# schematic.net
KiCad netlist of a schematic drawn in Altium Designer
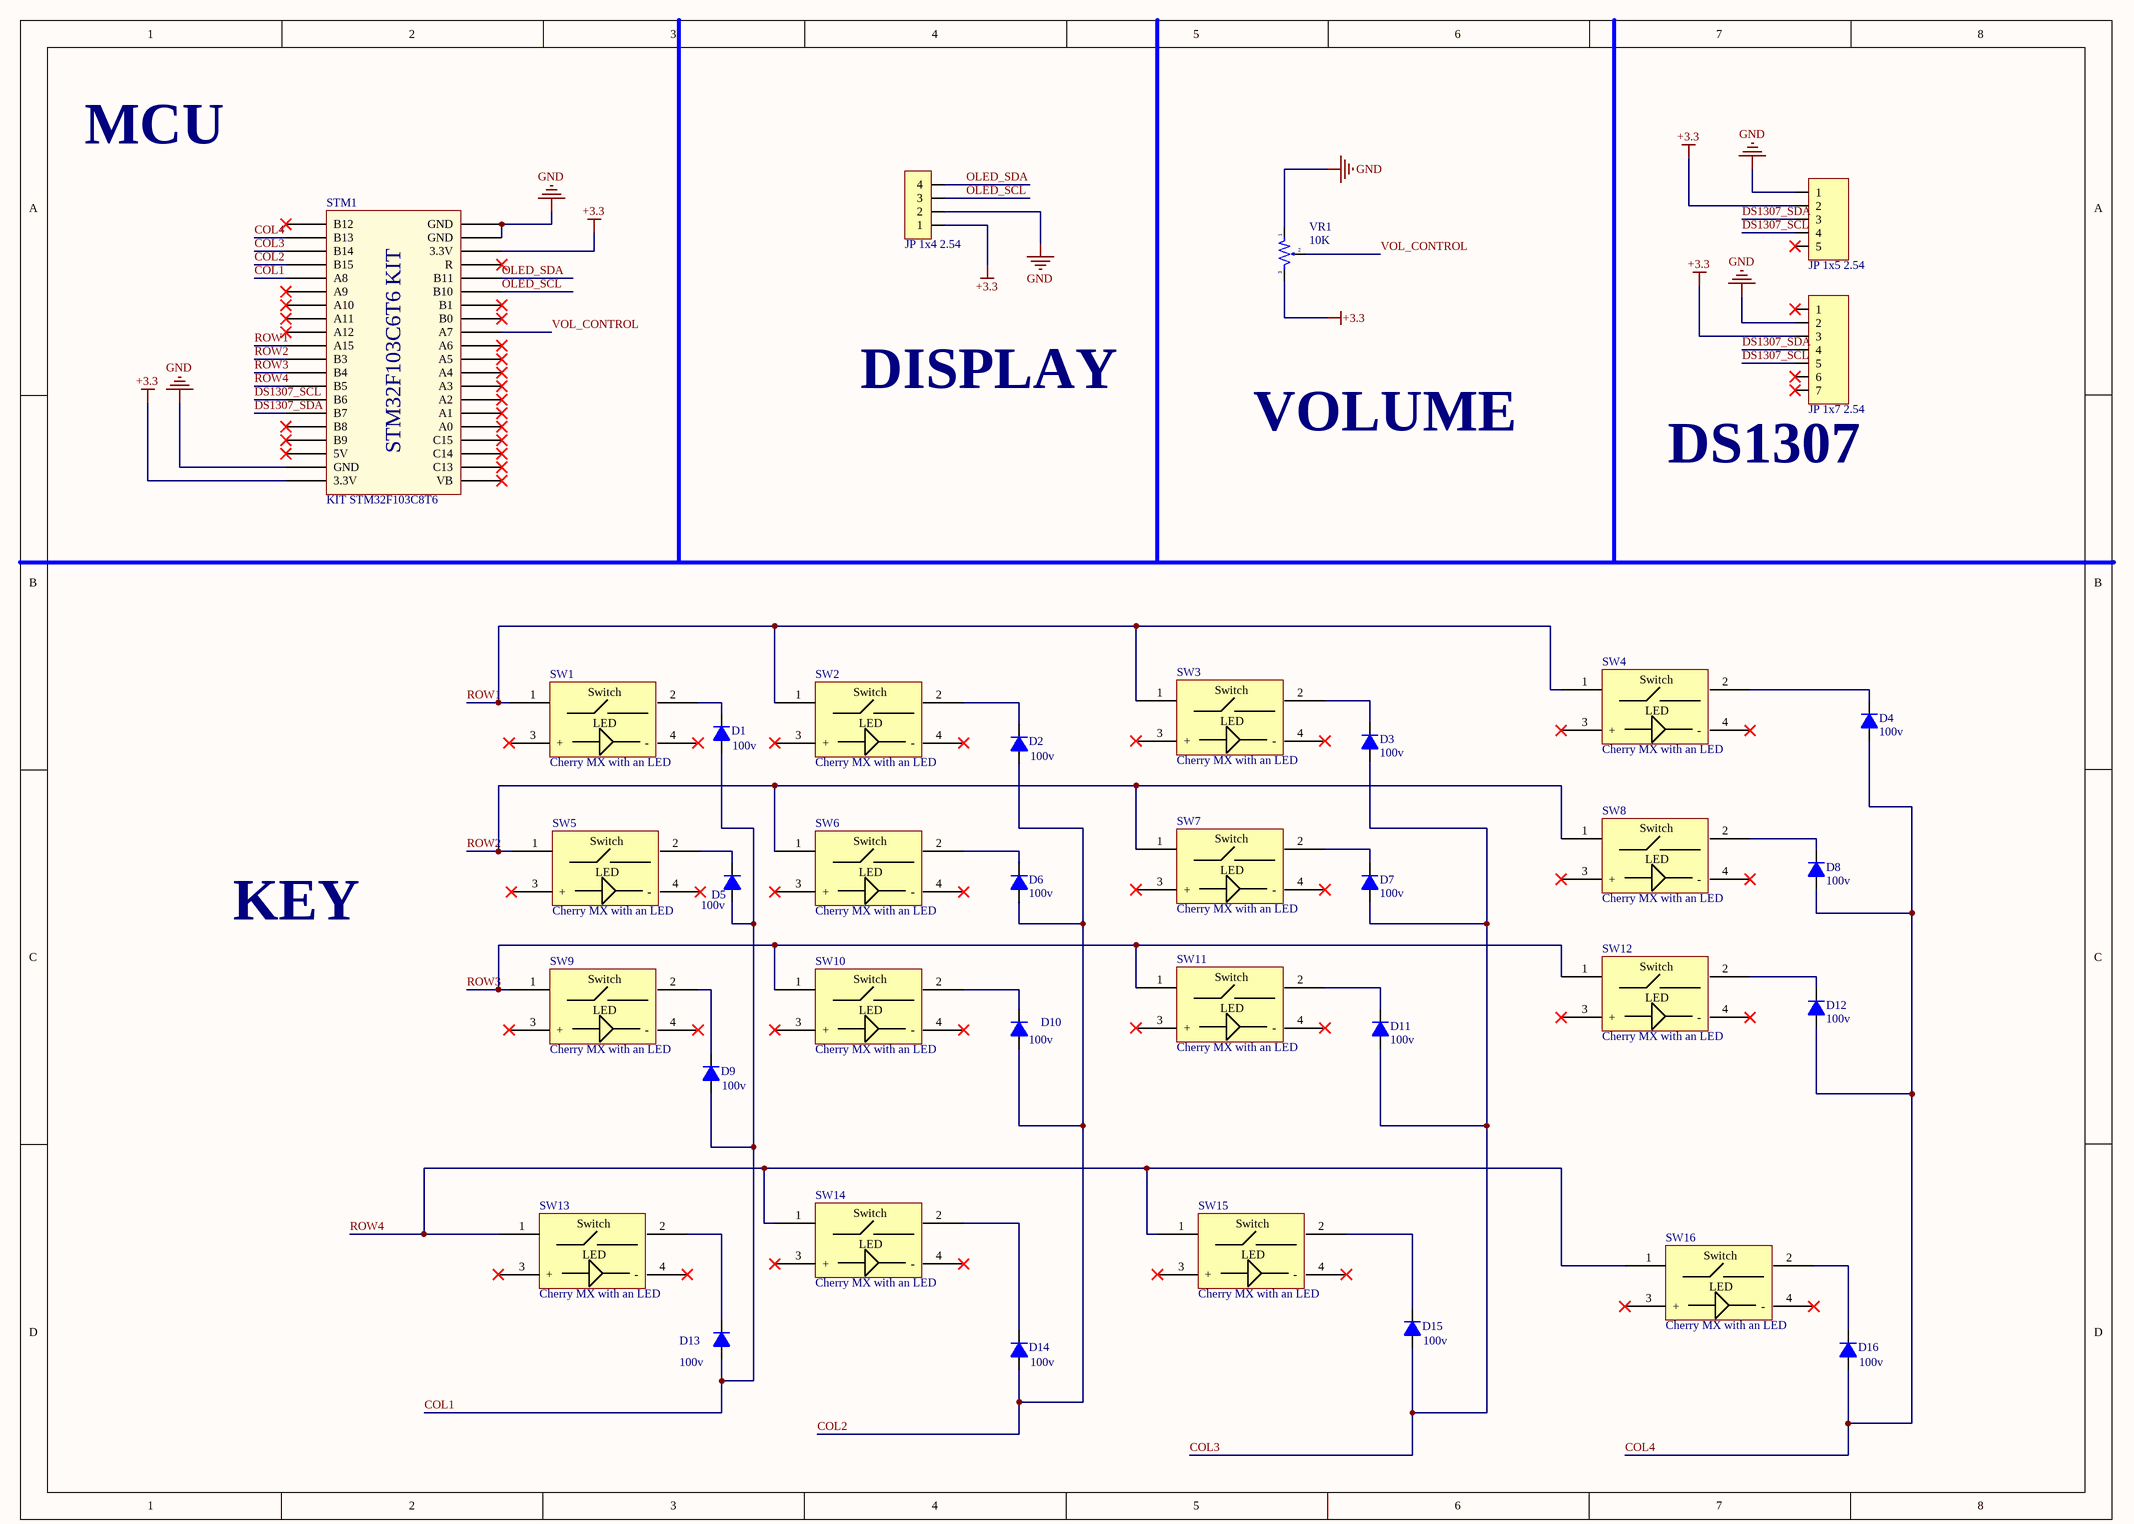
[diagram p0: schematic.SchDoc]

(export (version "E")
  (design (tool "Eeschema 10.0.6"))
  (components
    (comp (ref "D1")
      (value "100v")
      (footprint "DIODE 0.5A")
      (description "Cắm")
      (libsource (lib "Altium_Lib_by_KhueNguyenCreator") (part "Diode 1N4148"))
    )
    (comp (ref "D2")
      (value "100v")
      (footprint "DIODE 0.5A")
      (description "Cắm")
      (libsource (lib "Altium_Lib_by_KhueNguyenCreator") (part "Diode 1N4148"))
    )
    (comp (ref "D3")
      (value "100v")
      (footprint "DIODE 0.5A")
      (description "Cắm")
      (libsource (lib "Altium_Lib_by_KhueNguyenCreator") (part "Diode 1N4148"))
    )
    (comp (ref "D4")
      (value "100v")
      (footprint "DIODE 0.5A")
      (description "Cắm")
      (libsource (lib "Altium_Lib_by_KhueNguyenCreator") (part "Diode 1N4148"))
    )
    (comp (ref "D5")
      (value "100v")
      (footprint "DIODE 0.5A")
      (description "Cắm")
      (libsource (lib "Altium_Lib_by_KhueNguyenCreator") (part "Diode 1N4148"))
    )
    (comp (ref "D6")
      (value "100v")
      (footprint "DIODE 0.5A")
      (description "Cắm")
      (libsource (lib "Altium_Lib_by_KhueNguyenCreator") (part "Diode 1N4148"))
    )
    (comp (ref "D7")
      (value "100v")
      (footprint "DIODE 0.5A")
      (description "Cắm")
      (libsource (lib "Altium_Lib_by_KhueNguyenCreator") (part "Diode 1N4148"))
    )
    (comp (ref "D8")
      (value "100v")
      (footprint "DIODE 0.5A")
      (description "Cắm")
      (libsource (lib "Altium_Lib_by_KhueNguyenCreator") (part "Diode 1N4148"))
    )
    (comp (ref "D9")
      (value "100v")
      (footprint "DIODE 0.5A")
      (description "Cắm")
      (libsource (lib "Altium_Lib_by_KhueNguyenCreator") (part "Diode 1N4148"))
    )
    (comp (ref "D10")
      (value "100v")
      (footprint "DIODE 0.5A")
      (description "Cắm")
      (libsource (lib "Altium_Lib_by_KhueNguyenCreator") (part "Diode 1N4148"))
    )
    (comp (ref "D11")
      (value "100v")
      (footprint "DIODE 0.5A")
      (description "Cắm")
      (libsource (lib "Altium_Lib_by_KhueNguyenCreator") (part "Diode 1N4148"))
    )
    (comp (ref "D12")
      (value "100v")
      (footprint "DIODE 0.5A")
      (description "Cắm")
      (libsource (lib "Altium_Lib_by_KhueNguyenCreator") (part "Diode 1N4148"))
    )
    (comp (ref "D13")
      (value "100v")
      (footprint "DIODE 0.5A")
      (description "Cắm")
      (libsource (lib "Altium_Lib_by_KhueNguyenCreator") (part "Diode 1N4148"))
    )
    (comp (ref "D14")
      (value "100v")
      (footprint "DIODE 0.5A")
      (description "Cắm")
      (libsource (lib "Altium_Lib_by_KhueNguyenCreator") (part "Diode 1N4148"))
    )
    (comp (ref "D15")
      (value "100v")
      (footprint "DIODE 0.5A")
      (description "Cắm")
      (libsource (lib "Altium_Lib_by_KhueNguyenCreator") (part "Diode 1N4148"))
    )
    (comp (ref "D16")
      (value "100v")
      (footprint "DIODE 0.5A")
      (description "Cắm")
      (libsource (lib "Altium_Lib_by_KhueNguyenCreator") (part "Diode 1N4148"))
    )
    (comp (ref "JP1")
      (value "JP 1x4 2.54")
      (footprint "JP 1x4 CT")
      (description "Cắm")
      (libsource (lib "Altium_Lib_by_KhueNguyenCreator") (part "JP 1x4 2.54 Cai Thang"))
    )
    (comp (ref "JP2")
      (value "JP 1x5 2.54")
      (footprint "JP 1x5 CT")
      (description "Cắm")
      (libsource (lib "Altium_Lib_by_KhueNguyenCreator") (part "JP 1x5 2.54 Cai Thang"))
    )
    (comp (ref "JP3")
      (value "JP 1x7 2.54")
      (footprint "JP 1x7 CT")
      (description "Cắm")
      (libsource (lib "Altium_Lib_by_KhueNguyenCreator") (part "JP 1x7 2.54 Cai Thang"))
    )
    (comp (ref "STM1")
      (value "KIT STM32F103C8T6")
      (footprint "STM32F103 KIT")
      (description "KIT STM32F103C8T6 Bluepill")
      (libsource (lib "Altium_Lib_by_KhueNguyenCreator") (part "STM32f103 Bluepill"))
    )
    (comp (ref "SW1")
      (value "Cherry MX with an LED")
      (footprint "MX_Cherry_LED")
      (libsource (lib "PlumPot_Library") (part "MX_Cherry_LED"))
    )
    (comp (ref "SW2")
      (value "Cherry MX with an LED")
      (footprint "MX_Cherry_LED")
      (libsource (lib "PlumPot_Library") (part "MX_Cherry_LED"))
    )
    (comp (ref "SW3")
      (value "Cherry MX with an LED")
      (footprint "MX_Cherry_LED")
      (libsource (lib "PlumPot_Library") (part "MX_Cherry_LED"))
    )
    (comp (ref "SW4")
      (value "Cherry MX with an LED")
      (footprint "MX_Cherry_LED")
      (libsource (lib "PlumPot_Library") (part "MX_Cherry_LED"))
    )
    (comp (ref "SW5")
      (value "Cherry MX with an LED")
      (footprint "MX_Cherry_LED")
      (libsource (lib "PlumPot_Library") (part "MX_Cherry_LED"))
    )
    (comp (ref "SW6")
      (value "Cherry MX with an LED")
      (footprint "MX_Cherry_LED")
      (libsource (lib "PlumPot_Library") (part "MX_Cherry_LED"))
    )
    (comp (ref "SW7")
      (value "Cherry MX with an LED")
      (footprint "MX_Cherry_LED")
      (libsource (lib "PlumPot_Library") (part "MX_Cherry_LED"))
    )
    (comp (ref "SW8")
      (value "Cherry MX with an LED")
      (footprint "MX_Cherry_LED")
      (libsource (lib "PlumPot_Library") (part "MX_Cherry_LED"))
    )
    (comp (ref "SW9")
      (value "Cherry MX with an LED")
      (footprint "MX_Cherry_LED")
      (libsource (lib "PlumPot_Library") (part "MX_Cherry_LED"))
    )
    (comp (ref "SW10")
      (value "Cherry MX with an LED")
      (footprint "MX_Cherry_LED")
      (libsource (lib "PlumPot_Library") (part "MX_Cherry_LED"))
    )
    (comp (ref "SW11")
      (value "Cherry MX with an LED")
      (footprint "MX_Cherry_LED")
      (libsource (lib "PlumPot_Library") (part "MX_Cherry_LED"))
    )
    (comp (ref "SW12")
      (value "Cherry MX with an LED")
      (footprint "MX_Cherry_LED")
      (libsource (lib "PlumPot_Library") (part "MX_Cherry_LED"))
    )
    (comp (ref "SW13")
      (value "Cherry MX with an LED")
      (footprint "MX_Cherry_LED")
      (libsource (lib "PlumPot_Library") (part "MX_Cherry_LED"))
    )
    (comp (ref "SW14")
      (value "Cherry MX with an LED")
      (footprint "MX_Cherry_LED")
      (libsource (lib "PlumPot_Library") (part "MX_Cherry_LED"))
    )
    (comp (ref "SW15")
      (value "Cherry MX with an LED")
      (footprint "MX_Cherry_LED")
      (libsource (lib "PlumPot_Library") (part "MX_Cherry_LED"))
    )
    (comp (ref "SW16")
      (value "Cherry MX with an LED")
      (footprint "MX_Cherry_LED")
      (libsource (lib "PlumPot_Library") (part "MX_Cherry_LED"))
    )
    (comp (ref "VR1")
      (value "10K")
      (footprint "Bien Tro Volume Don")
      (description "Cắm")
      (libsource (lib "Altium_Lib_by_KhueNguyenCreator") (part "Triet Ap Don 10k"))
    )
  )
  (nets
    (net (code "1") (name "+3.3") (class "Default")
      (node (ref "JP1") (pin "1") (pinfunction "1_1") (pintype "passive"))
      (node (ref "JP2") (pin "2") (pinfunction "2_2") (pintype "passive"))
      (node (ref "JP3") (pin "3") (pinfunction "3_3") (pintype "passive"))
      (node (ref "STM1") (pin "20") (pinfunction "3.3V_20") (pintype "passive"))
      (node (ref "STM1") (pin "38") (pinfunction "3.3V_38") (pintype "passive"))
      (node (ref "VR1") (pin "3") (pinfunction "3_3") (pintype "passive"))
    )
    (net (code "2") (name "/COL1") (class "Default")
      (node (ref "D1") (pin "1") (pinfunction "A_1") (pintype "passive"))
      (node (ref "D13") (pin "1") (pinfunction "A_1") (pintype "passive"))
      (node (ref "D5") (pin "1") (pinfunction "A_1") (pintype "passive"))
      (node (ref "D9") (pin "1") (pinfunction "A_1") (pintype "passive"))
      (node (ref "STM1") (pin "5") (pinfunction "A8_5") (pintype "passive"))
    )
    (net (code "3") (name "/COL2") (class "Default")
      (node (ref "D10") (pin "1") (pinfunction "A_1") (pintype "passive"))
      (node (ref "D14") (pin "1") (pinfunction "A_1") (pintype "passive"))
      (node (ref "D2") (pin "1") (pinfunction "A_1") (pintype "passive"))
      (node (ref "D6") (pin "1") (pinfunction "A_1") (pintype "passive"))
      (node (ref "STM1") (pin "4") (pinfunction "B15_4") (pintype "passive"))
    )
    (net (code "4") (name "/COL3") (class "Default")
      (node (ref "D11") (pin "1") (pinfunction "A_1") (pintype "passive"))
      (node (ref "D15") (pin "1") (pinfunction "A_1") (pintype "passive"))
      (node (ref "D3") (pin "1") (pinfunction "A_1") (pintype "passive"))
      (node (ref "D7") (pin "1") (pinfunction "A_1") (pintype "passive"))
      (node (ref "STM1") (pin "3") (pinfunction "B14_3") (pintype "passive"))
    )
    (net (code "5") (name "/COL4") (class "Default")
      (node (ref "D12") (pin "1") (pinfunction "A_1") (pintype "passive"))
      (node (ref "D16") (pin "1") (pinfunction "A_1") (pintype "passive"))
      (node (ref "D4") (pin "1") (pinfunction "A_1") (pintype "passive"))
      (node (ref "D8") (pin "1") (pinfunction "A_1") (pintype "passive"))
      (node (ref "STM1") (pin "2") (pinfunction "B13_2") (pintype "passive"))
    )
    (net (code "6") (name "/DS1307_SCL") (class "Default")
      (node (ref "JP2") (pin "4") (pinfunction "4_4") (pintype "passive"))
      (node (ref "JP3") (pin "5") (pinfunction "5_5") (pintype "passive"))
      (node (ref "STM1") (pin "14") (pinfunction "B6_14") (pintype "passive"))
    )
    (net (code "7") (name "/DS1307_SDA") (class "Default")
      (node (ref "JP2") (pin "3") (pinfunction "3_3") (pintype "passive"))
      (node (ref "JP3") (pin "4") (pinfunction "4_4") (pintype "passive"))
      (node (ref "STM1") (pin "15") (pinfunction "B7_15") (pintype "passive"))
    )
    (net (code "8") (name "/OLED_SCL") (class "Default")
      (node (ref "JP1") (pin "3") (pinfunction "3_3") (pintype "passive"))
      (node (ref "STM1") (pin "35") (pinfunction "B10_35") (pintype "passive"))
    )
    (net (code "9") (name "/OLED_SDA") (class "Default")
      (node (ref "JP1") (pin "4") (pinfunction "4_4") (pintype "passive"))
      (node (ref "STM1") (pin "36") (pinfunction "B11_36") (pintype "passive"))
    )
    (net (code "10") (name "/ROW1") (class "Default")
      (node (ref "STM1") (pin "10") (pinfunction "A15_10") (pintype "passive"))
      (node (ref "SW1") (pin "1") (pintype "passive"))
      (node (ref "SW2") (pin "1") (pintype "passive"))
      (node (ref "SW3") (pin "1") (pintype "passive"))
      (node (ref "SW4") (pin "1") (pintype "passive"))
    )
    (net (code "11") (name "/ROW2") (class "Default")
      (node (ref "STM1") (pin "11") (pinfunction "B3_11") (pintype "passive"))
      (node (ref "SW5") (pin "1") (pintype "passive"))
      (node (ref "SW6") (pin "1") (pintype "passive"))
      (node (ref "SW7") (pin "1") (pintype "passive"))
      (node (ref "SW8") (pin "1") (pintype "passive"))
    )
    (net (code "12") (name "/ROW3") (class "Default")
      (node (ref "STM1") (pin "12") (pinfunction "B4_12") (pintype "passive"))
      (node (ref "SW10") (pin "1") (pintype "passive"))
      (node (ref "SW11") (pin "1") (pintype "passive"))
      (node (ref "SW12") (pin "1") (pintype "passive"))
      (node (ref "SW9") (pin "1") (pintype "passive"))
    )
    (net (code "13") (name "/ROW4") (class "Default")
      (node (ref "STM1") (pin "13") (pinfunction "B5_13") (pintype "passive"))
      (node (ref "SW13") (pin "1") (pintype "passive"))
      (node (ref "SW14") (pin "1") (pintype "passive"))
      (node (ref "SW15") (pin "1") (pintype "passive"))
      (node (ref "SW16") (pin "1") (pintype "passive"))
    )
    (net (code "14") (name "/VOL_CONTROL") (class "Default")
      (node (ref "STM1") (pin "32") (pinfunction "A7_32") (pintype "passive"))
      (node (ref "VR1") (pin "2") (pinfunction "2_2") (pintype "passive"))
    )
    (net (code "15") (name "GND") (class "Default")
      (node (ref "JP1") (pin "2") (pinfunction "2_2") (pintype "passive"))
      (node (ref "JP2") (pin "1") (pinfunction "1_1") (pintype "passive"))
      (node (ref "JP3") (pin "2") (pinfunction "2_2") (pintype "passive"))
      (node (ref "STM1") (pin "19") (pinfunction "GND_19") (pintype "passive"))
      (node (ref "STM1") (pin "39") (pinfunction "GND_39") (pintype "passive"))
      (node (ref "STM1") (pin "40") (pinfunction "GND_40") (pintype "passive"))
      (node (ref "VR1") (pin "1") (pinfunction "1_1") (pintype "passive"))
    )
    (net (code "16") (name "Net-(D1-K)") (class "Default")
      (node (ref "D1") (pin "2") (pinfunction "K_2") (pintype "passive"))
      (node (ref "SW1") (pin "2") (pintype "passive"))
    )
    (net (code "17") (name "Net-(D2-K)") (class "Default")
      (node (ref "D2") (pin "2") (pinfunction "K_2") (pintype "passive"))
      (node (ref "SW2") (pin "2") (pintype "passive"))
    )
    (net (code "18") (name "Net-(D3-K)") (class "Default")
      (node (ref "D3") (pin "2") (pinfunction "K_2") (pintype "passive"))
      (node (ref "SW3") (pin "2") (pintype "passive"))
    )
    (net (code "19") (name "Net-(D4-K)") (class "Default")
      (node (ref "D4") (pin "2") (pinfunction "K_2") (pintype "passive"))
      (node (ref "SW4") (pin "2") (pintype "passive"))
    )
    (net (code "20") (name "Net-(D5-K)") (class "Default")
      (node (ref "D5") (pin "2") (pinfunction "K_2") (pintype "passive"))
      (node (ref "SW5") (pin "2") (pintype "passive"))
    )
    (net (code "21") (name "Net-(D6-K)") (class "Default")
      (node (ref "D6") (pin "2") (pinfunction "K_2") (pintype "passive"))
      (node (ref "SW6") (pin "2") (pintype "passive"))
    )
    (net (code "22") (name "Net-(D7-K)") (class "Default")
      (node (ref "D7") (pin "2") (pinfunction "K_2") (pintype "passive"))
      (node (ref "SW7") (pin "2") (pintype "passive"))
    )
    (net (code "23") (name "Net-(D8-K)") (class "Default")
      (node (ref "D8") (pin "2") (pinfunction "K_2") (pintype "passive"))
      (node (ref "SW8") (pin "2") (pintype "passive"))
    )
    (net (code "24") (name "Net-(D9-K)") (class "Default")
      (node (ref "D9") (pin "2") (pinfunction "K_2") (pintype "passive"))
      (node (ref "SW9") (pin "2") (pintype "passive"))
    )
    (net (code "25") (name "Net-(D10-K)") (class "Default")
      (node (ref "D10") (pin "2") (pinfunction "K_2") (pintype "passive"))
      (node (ref "SW10") (pin "2") (pintype "passive"))
    )
    (net (code "26") (name "Net-(D11-K)") (class "Default")
      (node (ref "D11") (pin "2") (pinfunction "K_2") (pintype "passive"))
      (node (ref "SW11") (pin "2") (pintype "passive"))
    )
    (net (code "27") (name "Net-(D12-K)") (class "Default")
      (node (ref "D12") (pin "2") (pinfunction "K_2") (pintype "passive"))
      (node (ref "SW12") (pin "2") (pintype "passive"))
    )
    (net (code "28") (name "Net-(D13-K)") (class "Default")
      (node (ref "D13") (pin "2") (pinfunction "K_2") (pintype "passive"))
      (node (ref "SW13") (pin "2") (pintype "passive"))
    )
    (net (code "29") (name "Net-(D14-K)") (class "Default")
      (node (ref "D14") (pin "2") (pinfunction "K_2") (pintype "passive"))
      (node (ref "SW14") (pin "2") (pintype "passive"))
    )
    (net (code "30") (name "Net-(D15-K)") (class "Default")
      (node (ref "D15") (pin "2") (pinfunction "K_2") (pintype "passive"))
      (node (ref "SW15") (pin "2") (pintype "passive"))
    )
    (net (code "31") (name "Net-(D16-K)") (class "Default")
      (node (ref "D16") (pin "2") (pinfunction "K_2") (pintype "passive"))
      (node (ref "SW16") (pin "2") (pintype "passive"))
    )
    (net (code "32") (name "unconnected-(JP2-Pad5)") (class "Default")
      (node (ref "JP2") (pin "5") (pinfunction "5_5") (pintype "passive+no_connect"))
    )
    (net (code "33") (name "unconnected-(JP3-Pad1)") (class "Default")
      (node (ref "JP3") (pin "1") (pinfunction "1_1") (pintype "passive+no_connect"))
    )
    (net (code "34") (name "unconnected-(JP3-Pad6)") (class "Default")
      (node (ref "JP3") (pin "6") (pinfunction "6_6") (pintype "passive+no_connect"))
    )
    (net (code "35") (name "unconnected-(JP3-Pad7)") (class "Default")
      (node (ref "JP3") (pin "7") (pinfunction "7_7") (pintype "passive+no_connect"))
    )
    (net (code "36") (name "unconnected-(STM1-5V-Pad18)") (class "Default")
      (node (ref "STM1") (pin "18") (pinfunction "5V_18") (pintype "passive+no_connect"))
    )
    (net (code "37") (name "unconnected-(STM1-A0-Pad25)") (class "Default")
      (node (ref "STM1") (pin "25") (pinfunction "A0_25") (pintype "passive+no_connect"))
    )
    (net (code "38") (name "unconnected-(STM1-A1-Pad26)") (class "Default")
      (node (ref "STM1") (pin "26") (pinfunction "A1_26") (pintype "passive+no_connect"))
    )
    (net (code "39") (name "unconnected-(STM1-A2-Pad27)") (class "Default")
      (node (ref "STM1") (pin "27") (pinfunction "A2_27") (pintype "passive+no_connect"))
    )
    (net (code "40") (name "unconnected-(STM1-A3-Pad28)") (class "Default")
      (node (ref "STM1") (pin "28") (pinfunction "A3_28") (pintype "passive+no_connect"))
    )
    (net (code "41") (name "unconnected-(STM1-A4-Pad29)") (class "Default")
      (node (ref "STM1") (pin "29") (pinfunction "A4_29") (pintype "passive+no_connect"))
    )
    (net (code "42") (name "unconnected-(STM1-A5-Pad30)") (class "Default")
      (node (ref "STM1") (pin "30") (pinfunction "A5_30") (pintype "passive+no_connect"))
    )
    (net (code "43") (name "unconnected-(STM1-A6-Pad31)") (class "Default")
      (node (ref "STM1") (pin "31") (pinfunction "A6_31") (pintype "passive+no_connect"))
    )
    (net (code "44") (name "unconnected-(STM1-A9-Pad6)") (class "Default")
      (node (ref "STM1") (pin "6") (pinfunction "A9_6") (pintype "passive+no_connect"))
    )
    (net (code "45") (name "unconnected-(STM1-A10-Pad7)") (class "Default")
      (node (ref "STM1") (pin "7") (pinfunction "A10_7") (pintype "passive+no_connect"))
    )
    (net (code "46") (name "unconnected-(STM1-A11-Pad8)") (class "Default")
      (node (ref "STM1") (pin "8") (pinfunction "A11_8") (pintype "passive+no_connect"))
    )
    (net (code "47") (name "unconnected-(STM1-A12-Pad9)") (class "Default")
      (node (ref "STM1") (pin "9") (pinfunction "A12_9") (pintype "passive+no_connect"))
    )
    (net (code "48") (name "unconnected-(STM1-B0-Pad33)") (class "Default")
      (node (ref "STM1") (pin "33") (pinfunction "B0_33") (pintype "passive+no_connect"))
    )
    (net (code "49") (name "unconnected-(STM1-B1-Pad34)") (class "Default")
      (node (ref "STM1") (pin "34") (pinfunction "B1_34") (pintype "passive+no_connect"))
    )
    (net (code "50") (name "unconnected-(STM1-B8-Pad16)") (class "Default")
      (node (ref "STM1") (pin "16") (pinfunction "B8_16") (pintype "passive+no_connect"))
    )
    (net (code "51") (name "unconnected-(STM1-B9-Pad17)") (class "Default")
      (node (ref "STM1") (pin "17") (pinfunction "B9_17") (pintype "passive+no_connect"))
    )
    (net (code "52") (name "unconnected-(STM1-B12-Pad1)") (class "Default")
      (node (ref "STM1") (pin "1") (pinfunction "B12_1") (pintype "passive+no_connect"))
    )
    (net (code "53") (name "unconnected-(STM1-C13-Pad22)") (class "Default")
      (node (ref "STM1") (pin "22") (pinfunction "C13_22") (pintype "passive+no_connect"))
    )
    (net (code "54") (name "unconnected-(STM1-C14-Pad23)") (class "Default")
      (node (ref "STM1") (pin "23") (pinfunction "C14_23") (pintype "passive+no_connect"))
    )
    (net (code "55") (name "unconnected-(STM1-C15-Pad24)") (class "Default")
      (node (ref "STM1") (pin "24") (pinfunction "C15_24") (pintype "passive+no_connect"))
    )
    (net (code "56") (name "unconnected-(STM1-R-Pad37)") (class "Default")
      (node (ref "STM1") (pin "37") (pinfunction "R_37") (pintype "passive+no_connect"))
    )
    (net (code "57") (name "unconnected-(STM1-VB-Pad21)") (class "Default")
      (node (ref "STM1") (pin "21") (pinfunction "VB_21") (pintype "passive+no_connect"))
    )
    (net (code "58") (name "unconnected-(SW1-+-Pad3)") (class "Default")
      (node (ref "SW1") (pin "3") (pinfunction "+_3") (pintype "passive+no_connect"))
    )
    (net (code "59") (name "unconnected-(SW1---Pad4)") (class "Default")
      (node (ref "SW1") (pin "4") (pinfunction "-_4") (pintype "passive+no_connect"))
    )
    (net (code "60") (name "unconnected-(SW2-+-Pad3)") (class "Default")
      (node (ref "SW2") (pin "3") (pinfunction "+_3") (pintype "passive+no_connect"))
    )
    (net (code "61") (name "unconnected-(SW2---Pad4)") (class "Default")
      (node (ref "SW2") (pin "4") (pinfunction "-_4") (pintype "passive+no_connect"))
    )
    (net (code "62") (name "unconnected-(SW3-+-Pad3)") (class "Default")
      (node (ref "SW3") (pin "3") (pinfunction "+_3") (pintype "passive+no_connect"))
    )
    (net (code "63") (name "unconnected-(SW3---Pad4)") (class "Default")
      (node (ref "SW3") (pin "4") (pinfunction "-_4") (pintype "passive+no_connect"))
    )
    (net (code "64") (name "unconnected-(SW4-+-Pad3)") (class "Default")
      (node (ref "SW4") (pin "3") (pinfunction "+_3") (pintype "passive+no_connect"))
    )
    (net (code "65") (name "unconnected-(SW4---Pad4)") (class "Default")
      (node (ref "SW4") (pin "4") (pinfunction "-_4") (pintype "passive+no_connect"))
    )
    (net (code "66") (name "unconnected-(SW5-+-Pad3)") (class "Default")
      (node (ref "SW5") (pin "3") (pinfunction "+_3") (pintype "passive+no_connect"))
    )
    (net (code "67") (name "unconnected-(SW5---Pad4)") (class "Default")
      (node (ref "SW5") (pin "4") (pinfunction "-_4") (pintype "passive+no_connect"))
    )
    (net (code "68") (name "unconnected-(SW6-+-Pad3)") (class "Default")
      (node (ref "SW6") (pin "3") (pinfunction "+_3") (pintype "passive+no_connect"))
    )
    (net (code "69") (name "unconnected-(SW6---Pad4)") (class "Default")
      (node (ref "SW6") (pin "4") (pinfunction "-_4") (pintype "passive+no_connect"))
    )
    (net (code "70") (name "unconnected-(SW7-+-Pad3)") (class "Default")
      (node (ref "SW7") (pin "3") (pinfunction "+_3") (pintype "passive+no_connect"))
    )
    (net (code "71") (name "unconnected-(SW7---Pad4)") (class "Default")
      (node (ref "SW7") (pin "4") (pinfunction "-_4") (pintype "passive+no_connect"))
    )
    (net (code "72") (name "unconnected-(SW8-+-Pad3)") (class "Default")
      (node (ref "SW8") (pin "3") (pinfunction "+_3") (pintype "passive+no_connect"))
    )
    (net (code "73") (name "unconnected-(SW8---Pad4)") (class "Default")
      (node (ref "SW8") (pin "4") (pinfunction "-_4") (pintype "passive+no_connect"))
    )
    (net (code "74") (name "unconnected-(SW9-+-Pad3)") (class "Default")
      (node (ref "SW9") (pin "3") (pinfunction "+_3") (pintype "passive+no_connect"))
    )
    (net (code "75") (name "unconnected-(SW9---Pad4)") (class "Default")
      (node (ref "SW9") (pin "4") (pinfunction "-_4") (pintype "passive+no_connect"))
    )
    (net (code "76") (name "unconnected-(SW10-+-Pad3)") (class "Default")
      (node (ref "SW10") (pin "3") (pinfunction "+_3") (pintype "passive+no_connect"))
    )
    (net (code "77") (name "unconnected-(SW10---Pad4)") (class "Default")
      (node (ref "SW10") (pin "4") (pinfunction "-_4") (pintype "passive+no_connect"))
    )
    (net (code "78") (name "unconnected-(SW11-+-Pad3)") (class "Default")
      (node (ref "SW11") (pin "3") (pinfunction "+_3") (pintype "passive+no_connect"))
    )
    (net (code "79") (name "unconnected-(SW11---Pad4)") (class "Default")
      (node (ref "SW11") (pin "4") (pinfunction "-_4") (pintype "passive+no_connect"))
    )
    (net (code "80") (name "unconnected-(SW12-+-Pad3)") (class "Default")
      (node (ref "SW12") (pin "3") (pinfunction "+_3") (pintype "passive+no_connect"))
    )
    (net (code "81") (name "unconnected-(SW12---Pad4)") (class "Default")
      (node (ref "SW12") (pin "4") (pinfunction "-_4") (pintype "passive+no_connect"))
    )
    (net (code "82") (name "unconnected-(SW13-+-Pad3)") (class "Default")
      (node (ref "SW13") (pin "3") (pinfunction "+_3") (pintype "passive+no_connect"))
    )
    (net (code "83") (name "unconnected-(SW13---Pad4)") (class "Default")
      (node (ref "SW13") (pin "4") (pinfunction "-_4") (pintype "passive+no_connect"))
    )
    (net (code "84") (name "unconnected-(SW14-+-Pad3)") (class "Default")
      (node (ref "SW14") (pin "3") (pinfunction "+_3") (pintype "passive+no_connect"))
    )
    (net (code "85") (name "unconnected-(SW14---Pad4)") (class "Default")
      (node (ref "SW14") (pin "4") (pinfunction "-_4") (pintype "passive+no_connect"))
    )
    (net (code "86") (name "unconnected-(SW15-+-Pad3)") (class "Default")
      (node (ref "SW15") (pin "3") (pinfunction "+_3") (pintype "passive+no_connect"))
    )
    (net (code "87") (name "unconnected-(SW15---Pad4)") (class "Default")
      (node (ref "SW15") (pin "4") (pinfunction "-_4") (pintype "passive+no_connect"))
    )
    (net (code "88") (name "unconnected-(SW16-+-Pad3)") (class "Default")
      (node (ref "SW16") (pin "3") (pinfunction "+_3") (pintype "passive+no_connect"))
    )
    (net (code "89") (name "unconnected-(SW16---Pad4)") (class "Default")
      (node (ref "SW16") (pin "4") (pinfunction "-_4") (pintype "passive+no_connect"))
    )
  )
)
